# 2015-02-06_16-54-561.net
KiCad netlist of a schematic drawn in Altium Designer
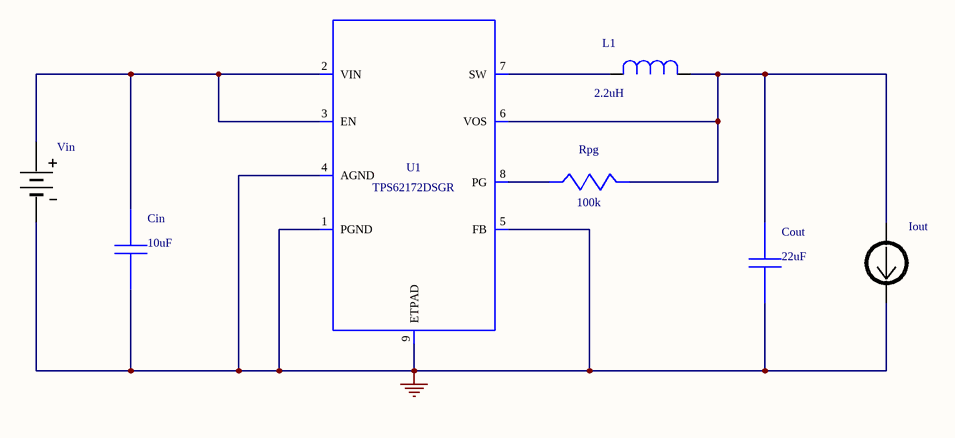
[diagram p0: 2015-02-06_16-54-561.schdoc]

(export (version "E")
  (design (tool "Eeschema 10.0.6"))
  (components
    (comp (ref "Cin")
      (value "10uF")
      (description "GRM219R61E106KA1")
      (fields (field (name "MANUFACTURER PART NUMBER") "GRM219R61E106KA12"))
      (libsource (lib "TI WEBENCH") (part "Cin"))
    )
    (comp (ref "Cout")
      (value "22uF")
      (description "GRM31CR70J226KE1")
      (fields (field (name "MANUFACTURER PART NUMBER") "GRM31CR70J226KE19L"))
      (libsource (lib "TI WEBENCH") (part "Cout"))
    )
    (comp (ref "Iout")
      (value "WB_CURRENT_LOAD")
      (description "Imported")
      (libsource (lib "TI WEBENCH") (part "WB_CURRENT_LOAD"))
    )
    (comp (ref "L1")
      (value "2.2uH")
      (description "VLF252015MT-2R2M")
      (fields (field (name "MANUFACTURER PART NUMBER") "'VLF252015MT-2R2M'"))
      (libsource (lib "TI WEBENCH") (part "L1"))
    )
    (comp (ref "Rpg")
      (value "100k")
      (description "CRCW0402100KFKED")
      (libsource (lib "TI WEBENCH") (part "Rpg"))
    )
    (comp (ref "U1")
      (value "TPS62172DSGR")
      (fields (field (name "PACKAGEREFERENCE") "TPS62172DSGR"))
      (libsource (lib "TI WEBENCH") (part "U1"))
    )
    (comp (ref "Vin")
      (value "WB_BATTERY")
      (description "Imported")
      (libsource (lib "TI WEBENCH") (part "WB_BATTERY"))
    )
  )
  (nets
    (net (code "1") (name "0") (class "Default")
      (node (ref "Cin") (pin "2") (pinfunction "2_2") (pintype "passive"))
      (node (ref "Cout") (pin "2") (pinfunction "2_2") (pintype "passive"))
      (node (ref "Iout") (pin "2") (pinfunction "-_2") (pintype "passive"))
      (node (ref "U1") (pin "1") (pinfunction "PGND_1") (pintype "passive"))
      (node (ref "U1") (pin "4") (pinfunction "AGND_4") (pintype "passive"))
      (node (ref "U1") (pin "5") (pinfunction "FB_5") (pintype "passive"))
      (node (ref "U1") (pin "9") (pinfunction "ETPAD_9") (pintype "passive"))
      (node (ref "Vin") (pin "2") (pinfunction "-_2") (pintype "passive"))
    )
    (net (code "2") (name "Net-(Iout-+)") (class "Default")
      (node (ref "Cout") (pin "1") (pinfunction "1_1") (pintype "passive"))
      (node (ref "Iout") (pin "1") (pinfunction "+_1") (pintype "passive"))
      (node (ref "L1") (pin "1") (pintype "passive"))
      (node (ref "Rpg") (pin "1") (pinfunction "1_1") (pintype "passive"))
      (node (ref "U1") (pin "6") (pinfunction "VOS_6") (pintype "passive"))
    )
    (net (code "3") (name "Net-(U1-EN)") (class "Default")
      (node (ref "Cin") (pin "1") (pinfunction "1_1") (pintype "passive"))
      (node (ref "U1") (pin "2") (pinfunction "VIN_2") (pintype "passive"))
      (node (ref "U1") (pin "3") (pinfunction "EN_3") (pintype "passive"))
      (node (ref "Vin") (pin "1") (pinfunction "+_1") (pintype "passive"))
    )
    (net (code "4") (name "Net-(U1-PG)") (class "Default")
      (node (ref "Rpg") (pin "2") (pinfunction "2_2") (pintype "passive"))
      (node (ref "U1") (pin "8") (pinfunction "PG_8") (pintype "passive"))
    )
    (net (code "5") (name "Net-(U1-SW)") (class "Default")
      (node (ref "L1") (pin "2") (pintype "passive"))
      (node (ref "U1") (pin "7") (pinfunction "SW_7") (pintype "passive"))
    )
  )
)
